# STLink_v21.net
KiCad netlist of a schematic drawn in EAGLE
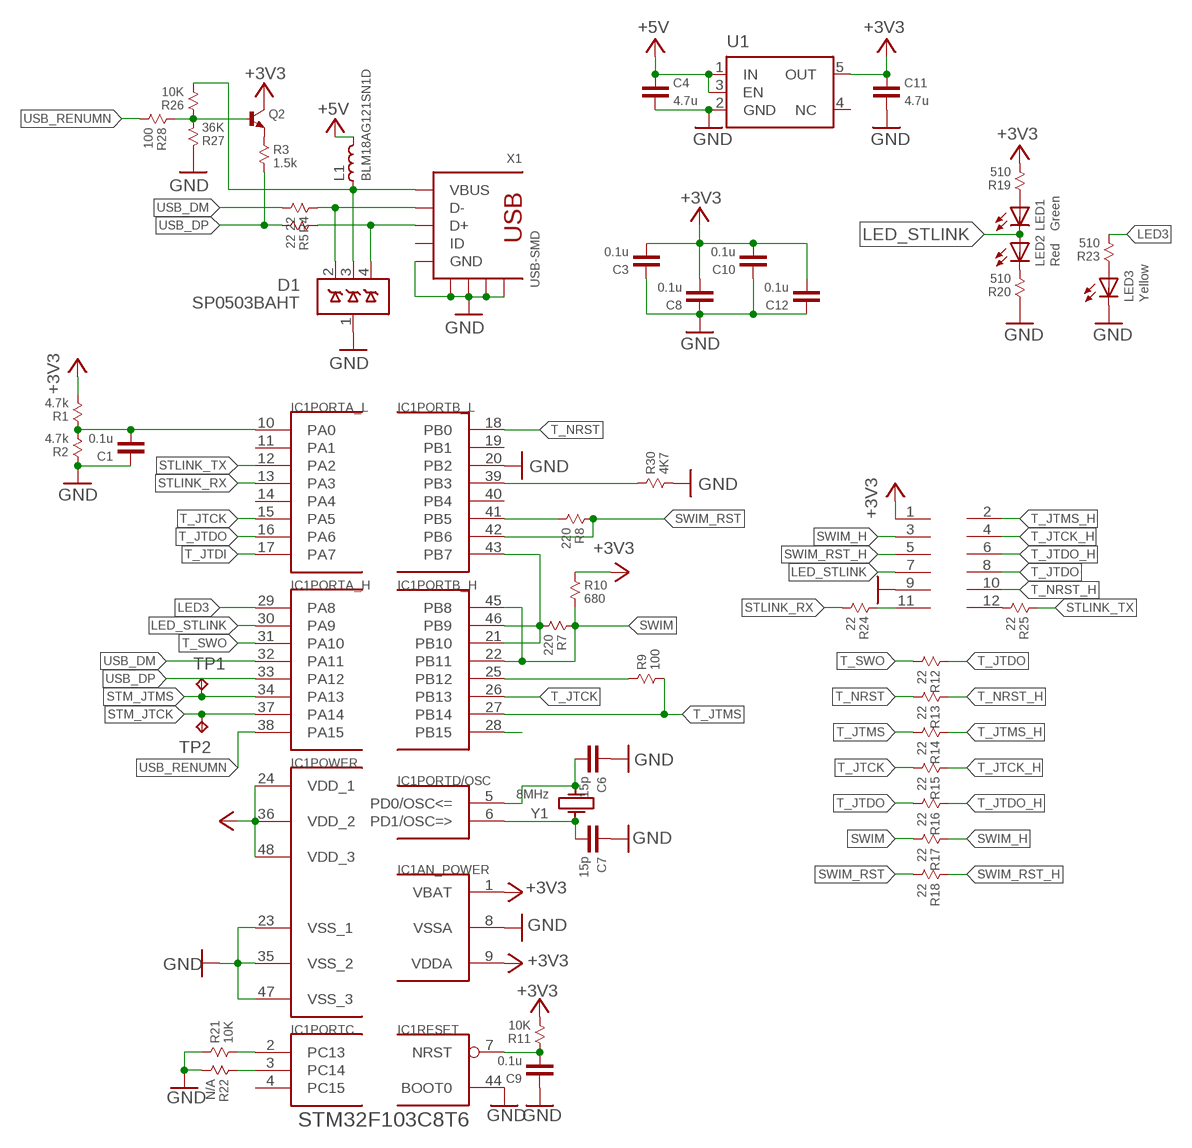
[diagram p0: schematic, sheet 1]

(export (version "E")
  (design (tool "Eeschema 10.0.6"))
  (components
    (comp (ref "C1")
      (value "0.1u")
      (footprint "eagle-import:0603")
      (libsource (lib "eagle-import") (part "CAP-0603"))
    )
    (comp (ref "C3")
      (value "0.1u")
      (footprint "eagle-import:0603")
      (libsource (lib "eagle-import") (part "CAP-0603"))
    )
    (comp (ref "C4")
      (value "4.7u")
      (footprint "eagle-import:0603")
      (libsource (lib "eagle-import") (part "CAP-0603"))
    )
    (comp (ref "C6")
      (value "15p")
      (footprint "eagle-import:0603")
      (libsource (lib "eagle-import") (part "CAP-0603"))
    )
    (comp (ref "C7")
      (value "15p")
      (footprint "eagle-import:0603")
      (libsource (lib "eagle-import") (part "CAP-0603"))
    )
    (comp (ref "C8")
      (value "0.1u")
      (footprint "eagle-import:0603")
      (libsource (lib "eagle-import") (part "CAP-0603"))
    )
    (comp (ref "C9")
      (value "0.1u")
      (footprint "eagle-import:0603")
      (libsource (lib "eagle-import") (part "CAP-0603"))
    )
    (comp (ref "C10")
      (value "0.1u")
      (footprint "eagle-import:0603")
      (libsource (lib "eagle-import") (part "CAP-0603"))
    )
    (comp (ref "C11")
      (value "4.7u")
      (footprint "eagle-import:0603")
      (libsource (lib "eagle-import") (part "CAP-0603"))
    )
    (comp (ref "C12")
      (value "0.1u")
      (footprint "eagle-import:0603")
      (libsource (lib "eagle-import") (part "CAP-0603"))
    )
    (comp (ref "CN2")
      (value "M06X2")
      (footprint "eagle-import:PLANAR-6X2")
      (libsource (lib "eagle-import") (part "M06X2"))
    )
    (comp (ref "D1")
      (value "SP0503BAHT")
      (footprint "eagle-import:SOT143")
      (libsource (lib "eagle-import") (part "SP0503BAHT"))
    )
    (comp (ref "IC1")
      (value "STM32F103C8T6")
      (footprint "eagle-import:TQFP48")
      (libsource (lib "eagle-import") (part "STM32F10XCXT6"))
    )
    (comp (ref "L1")
      (value "BLM18AG121SN1D")
      (footprint "eagle-import:0603")
      (libsource (lib "eagle-import") (part "INDUCTOR-0603"))
    )
    (comp (ref "LED1")
      (value "Green")
      (footprint "eagle-import:CHIP-LED0603")
      (libsource (lib "eagle-import") (part "LEDCHIP-LED0603"))
    )
    (comp (ref "LED2")
      (value "Red")
      (footprint "eagle-import:CHIP-LED0603")
      (libsource (lib "eagle-import") (part "LEDCHIP-LED0603"))
    )
    (comp (ref "LED3")
      (value "Yellow")
      (footprint "eagle-import:CHIP-LED0603")
      (libsource (lib "eagle-import") (part "LEDCHIP-LED0603"))
    )
    (comp (ref "Q2")
      (value "NPNBC847")
      (footprint "eagle-import:SOT-23")
      (libsource (lib "eagle-import") (part "NPNBC847"))
    )
    (comp (ref "R1")
      (value "4.7k")
      (footprint "eagle-import:0603")
      (libsource (lib "eagle-import") (part "RESISTOR-0603"))
    )
    (comp (ref "R2")
      (value "4.7k")
      (footprint "eagle-import:0603")
      (libsource (lib "eagle-import") (part "RESISTOR-0603"))
    )
    (comp (ref "R3")
      (value "1.5k")
      (footprint "eagle-import:0603")
      (libsource (lib "eagle-import") (part "RESISTOR-0603"))
    )
    (comp (ref "R4")
      (value "22")
      (footprint "eagle-import:0603")
      (libsource (lib "eagle-import") (part "RESISTOR-0603"))
    )
    (comp (ref "R5")
      (value "22")
      (footprint "eagle-import:0603")
      (libsource (lib "eagle-import") (part "RESISTOR-0603"))
    )
    (comp (ref "R7")
      (value "220")
      (footprint "eagle-import:0603")
      (libsource (lib "eagle-import") (part "RESISTOR-0603"))
    )
    (comp (ref "R8")
      (value "220")
      (footprint "eagle-import:0603")
      (libsource (lib "eagle-import") (part "RESISTOR-0603"))
    )
    (comp (ref "R9")
      (value "100")
      (footprint "eagle-import:0603")
      (libsource (lib "eagle-import") (part "RESISTOR-0603"))
    )
    (comp (ref "R10")
      (value "680")
      (footprint "eagle-import:0603")
      (libsource (lib "eagle-import") (part "RESISTOR-0603"))
    )
    (comp (ref "R11")
      (value "10K")
      (footprint "eagle-import:0603")
      (libsource (lib "eagle-import") (part "RESISTOR-0603"))
    )
    (comp (ref "R12")
      (value "22")
      (footprint "eagle-import:0603")
      (libsource (lib "eagle-import") (part "RESISTOR-0603"))
    )
    (comp (ref "R13")
      (value "22")
      (footprint "eagle-import:0603")
      (libsource (lib "eagle-import") (part "RESISTOR-0603"))
    )
    (comp (ref "R14")
      (value "22")
      (footprint "eagle-import:0603")
      (libsource (lib "eagle-import") (part "RESISTOR-0603"))
    )
    (comp (ref "R15")
      (value "22")
      (footprint "eagle-import:0603")
      (libsource (lib "eagle-import") (part "RESISTOR-0603"))
    )
    (comp (ref "R16")
      (value "22")
      (footprint "eagle-import:0603")
      (libsource (lib "eagle-import") (part "RESISTOR-0603"))
    )
    (comp (ref "R17")
      (value "22")
      (footprint "eagle-import:0603")
      (libsource (lib "eagle-import") (part "RESISTOR-0603"))
    )
    (comp (ref "R18")
      (value "22")
      (footprint "eagle-import:0603")
      (libsource (lib "eagle-import") (part "RESISTOR-0603"))
    )
    (comp (ref "R19")
      (value "510")
      (footprint "eagle-import:0603")
      (libsource (lib "eagle-import") (part "RESISTOR-0603"))
    )
    (comp (ref "R20")
      (value "510")
      (footprint "eagle-import:0603")
      (libsource (lib "eagle-import") (part "RESISTOR-0603"))
    )
    (comp (ref "R21")
      (value "10K")
      (footprint "eagle-import:0603")
      (libsource (lib "eagle-import") (part "RESISTOR-0603"))
    )
    (comp (ref "R22")
      (value "N/A")
      (footprint "eagle-import:0603")
      (libsource (lib "eagle-import") (part "RESISTOR-0603"))
    )
    (comp (ref "R23")
      (value "510")
      (footprint "eagle-import:0603")
      (libsource (lib "eagle-import") (part "RESISTOR-0603"))
    )
    (comp (ref "R24")
      (value "22")
      (footprint "eagle-import:0603")
      (libsource (lib "eagle-import") (part "RESISTOR-0603"))
    )
    (comp (ref "R25")
      (value "22")
      (footprint "eagle-import:0603")
      (libsource (lib "eagle-import") (part "RESISTOR-0603"))
    )
    (comp (ref "R26")
      (value "10K")
      (footprint "eagle-import:0603")
      (libsource (lib "eagle-import") (part "RESISTOR-0603"))
    )
    (comp (ref "R27")
      (value "36K")
      (footprint "eagle-import:0603")
      (libsource (lib "eagle-import") (part "RESISTOR-0603"))
    )
    (comp (ref "R28")
      (value "100")
      (footprint "eagle-import:0603")
      (libsource (lib "eagle-import") (part "RESISTOR-0603"))
    )
    (comp (ref "R30")
      (value "4K7")
      (footprint "eagle-import:0603")
      (libsource (lib "eagle-import") (part "RESISTOR-0603"))
    )
    (comp (ref "TP1")
      (value "TPTP10R")
      (footprint "eagle-import:TP10R")
      (libsource (lib "eagle-import") (part "TPTP10R"))
    )
    (comp (ref "TP2")
      (value "TPTP10R")
      (footprint "eagle-import:TP10R")
      (libsource (lib "eagle-import") (part "TPTP10R"))
    )
    (comp (ref "U1")
      (value "TPS73033")
      (footprint "eagle-import:SOT23-5")
      (libsource (lib "eagle-import") (part "TPS73033"))
    )
    (comp (ref "X1")
      (value "USB-SMD")
      (footprint "eagle-import:USB-MINIB")
      (libsource (lib "eagle-import") (part "USB-SMD"))
    )
    (comp (ref "Y1")
      (value "8MHz")
      (footprint "eagle-import:C0532")
      (libsource (lib "eagle-import") (part "CRYSTAL-0532"))
    )
  )
  (nets
    (net (code "1") (name "+3V3") (class "Default")
      (node (ref "C10") (pin "1") (pinfunction "1_1") (pintype "passive"))
      (node (ref "C11") (pin "2") (pinfunction "2_2") (pintype "passive"))
      (node (ref "C12") (pin "1") (pinfunction "1_1") (pintype "passive"))
      (node (ref "C3") (pin "1") (pinfunction "1_1") (pintype "passive"))
      (node (ref "C8") (pin "1") (pinfunction "1_1") (pintype "passive"))
      (node (ref "CN2") (pin "1") (pinfunction "1_1") (pintype "bidirectional"))
      (node (ref "IC1") (pin "1") (pinfunction "VBAT_1") (pintype "power_in"))
      (node (ref "IC1") (pin "24") (pinfunction "VDD_1_24") (pintype "power_in"))
      (node (ref "IC1") (pin "36") (pinfunction "VDD_2_36") (pintype "power_in"))
      (node (ref "IC1") (pin "48") (pinfunction "VDD_3_48") (pintype "power_in"))
      (node (ref "IC1") (pin "9") (pinfunction "VDDA_9") (pintype "power_in"))
      (node (ref "Q2") (pin "3") (pinfunction "C_3") (pintype "passive"))
      (node (ref "R1") (pin "2") (pinfunction "2_2") (pintype "passive"))
      (node (ref "R10") (pin "1") (pinfunction "1_1") (pintype "passive"))
      (node (ref "R11") (pin "2") (pinfunction "2_2") (pintype "passive"))
      (node (ref "R19") (pin "2") (pinfunction "2_2") (pintype "passive"))
      (node (ref "U1") (pin "5") (pinfunction "OUT_5") (pintype "passive"))
    )
    (net (code "2") (name "+5V") (class "Default")
      (node (ref "C4") (pin "2") (pinfunction "2_2") (pintype "passive"))
      (node (ref "L1") (pin "2") (pinfunction "2_2") (pintype "passive"))
      (node (ref "U1") (pin "1") (pinfunction "IN_1") (pintype "passive"))
      (node (ref "U1") (pin "3") (pinfunction "EN_3") (pintype "input"))
    )
    (net (code "3") (name "GND") (class "Default")
      (node (ref "C1") (pin "2") (pinfunction "2_2") (pintype "passive"))
      (node (ref "C10") (pin "2") (pinfunction "2_2") (pintype "passive"))
      (node (ref "C11") (pin "1") (pinfunction "1_1") (pintype "passive"))
      (node (ref "C12") (pin "2") (pinfunction "2_2") (pintype "passive"))
      (node (ref "C3") (pin "2") (pinfunction "2_2") (pintype "passive"))
      (node (ref "C4") (pin "1") (pinfunction "1_1") (pintype "passive"))
      (node (ref "C6") (pin "2") (pinfunction "2_2") (pintype "passive"))
      (node (ref "C7") (pin "2") (pinfunction "2_2") (pintype "passive"))
      (node (ref "C8") (pin "2") (pinfunction "2_2") (pintype "passive"))
      (node (ref "C9") (pin "2") (pinfunction "2_2") (pintype "passive"))
      (node (ref "CN2") (pin "9") (pinfunction "9_9") (pintype "bidirectional"))
      (node (ref "D1") (pin "1") (pinfunction "GND_1") (pintype "power_in"))
      (node (ref "IC1") (pin "20") (pinfunction "PB2_20") (pintype "bidirectional"))
      (node (ref "IC1") (pin "23") (pinfunction "VSS_1_23") (pintype "power_in"))
      (node (ref "IC1") (pin "35") (pinfunction "VSS_2_35") (pintype "power_in"))
      (node (ref "IC1") (pin "44") (pinfunction "BOOT0_44") (pintype "input"))
      (node (ref "IC1") (pin "47") (pinfunction "VSS_3_47") (pintype "power_in"))
      (node (ref "IC1") (pin "8") (pinfunction "VSSA_8") (pintype "power_in"))
      (node (ref "LED3") (pin "C") (pinfunction "C_C") (pintype "passive"))
      (node (ref "R2") (pin "1") (pinfunction "1_1") (pintype "passive"))
      (node (ref "R20") (pin "1") (pinfunction "1_1") (pintype "passive"))
      (node (ref "R21") (pin "1") (pinfunction "1_1") (pintype "passive"))
      (node (ref "R22") (pin "2") (pinfunction "2_2") (pintype "passive"))
      (node (ref "R27") (pin "1") (pinfunction "1_1") (pintype "passive"))
      (node (ref "R30") (pin "2") (pinfunction "2_2") (pintype "passive"))
      (node (ref "U1") (pin "2") (pinfunction "GND_2") (pintype "power_in"))
      (node (ref "X1") (pin "GND") (pinfunction "GND_GND") (pintype "power_in"))
      (node (ref "X1") (pin "GND@1") (pinfunction "GND_GND@1") (pintype "power_in"))
      (node (ref "X1") (pin "GND@2") (pinfunction "GND_GND@2") (pintype "power_in"))
      (node (ref "X1") (pin "GND@3") (pinfunction "GND_GND@3") (pintype "power_in"))
      (node (ref "X1") (pin "GND@4") (pinfunction "GND_GND@4") (pintype "power_in"))
    )
    (net (code "4") (name "LED3") (class "Default")
      (node (ref "IC1") (pin "29") (pinfunction "PA8_29") (pintype "bidirectional"))
      (node (ref "R23") (pin "2") (pinfunction "2_2") (pintype "passive"))
    )
    (net (code "5") (name "LED_STLINK") (class "Default")
      (node (ref "CN2") (pin "7") (pinfunction "7_7") (pintype "bidirectional"))
      (node (ref "IC1") (pin "30") (pinfunction "PA9_30") (pintype "bidirectional"))
      (node (ref "LED1") (pin "C") (pinfunction "C_C") (pintype "passive"))
      (node (ref "LED2") (pin "A") (pinfunction "A_A") (pintype "passive"))
    )
    (net (code "6") (name "Net-(CN2-Pad11)") (class "Default")
      (node (ref "CN2") (pin "11") (pinfunction "11_11") (pintype "bidirectional"))
      (node (ref "R24") (pin "1") (pinfunction "1_1") (pintype "passive"))
    )
    (net (code "7") (name "Net-(CN2-Pad12)") (class "Default")
      (node (ref "CN2") (pin "12") (pinfunction "12_12") (pintype "bidirectional"))
      (node (ref "R25") (pin "2") (pinfunction "2_2") (pintype "passive"))
    )
    (net (code "8") (name "Net-(D1-D1)") (class "Default")
      (node (ref "D1") (pin "2") (pinfunction "D1_2") (pintype "passive"))
      (node (ref "R4") (pin "1") (pinfunction "1_1") (pintype "passive"))
      (node (ref "X1") (pin "D-") (pinfunction "D-_D-") (pintype "bidirectional"))
    )
    (net (code "9") (name "Net-(D1-D2)") (class "Default")
      (node (ref "D1") (pin "3") (pinfunction "D2_3") (pintype "passive"))
      (node (ref "L1") (pin "1") (pinfunction "1_1") (pintype "passive"))
      (node (ref "R26") (pin "2") (pinfunction "2_2") (pintype "passive"))
      (node (ref "X1") (pin "VBUS") (pinfunction "VBUS_VBUS") (pintype "passive"))
    )
    (net (code "10") (name "Net-(D1-D3)") (class "Default")
      (node (ref "D1") (pin "4") (pinfunction "D3_4") (pintype "passive"))
      (node (ref "R5") (pin "1") (pinfunction "1_1") (pintype "passive"))
      (node (ref "X1") (pin "D+") (pinfunction "D+_D+") (pintype "bidirectional"))
    )
    (net (code "11") (name "Net-(IC1C-PA0)") (class "Default")
      (node (ref "C1") (pin "1") (pinfunction "1_1") (pintype "passive"))
      (node (ref "IC1") (pin "10") (pinfunction "PA0_10") (pintype "bidirectional"))
      (node (ref "R1") (pin "1") (pinfunction "1_1") (pintype "passive"))
      (node (ref "R2") (pin "2") (pinfunction "2_2") (pintype "passive"))
    )
    (net (code "12") (name "Net-(IC1D-PB10)") (class "Default")
      (node (ref "IC1") (pin "21") (pinfunction "PB10_21") (pintype "bidirectional"))
      (node (ref "IC1") (pin "43") (pinfunction "PB7_43") (pintype "bidirectional"))
      (node (ref "IC1") (pin "46") (pinfunction "PB9_46") (pintype "bidirectional"))
      (node (ref "R7") (pin "2") (pinfunction "2_2") (pintype "passive"))
    )
    (net (code "13") (name "Net-(IC1D-PB12)") (class "Default")
      (node (ref "IC1") (pin "25") (pinfunction "PB12_25") (pintype "bidirectional"))
      (node (ref "R9") (pin "1") (pinfunction "1_1") (pintype "passive"))
    )
    (net (code "14") (name "Net-(IC1E-PB3)") (class "Default")
      (node (ref "IC1") (pin "39") (pinfunction "PB3_39") (pintype "bidirectional"))
      (node (ref "R30") (pin "1") (pinfunction "1_1") (pintype "passive"))
    )
    (net (code "15") (name "Net-(IC1E-PB5)") (class "Default")
      (node (ref "IC1") (pin "41") (pinfunction "PB5_41") (pintype "bidirectional"))
      (node (ref "R8") (pin "2") (pinfunction "2_2") (pintype "passive"))
    )
    (net (code "16") (name "Net-(IC1F-PC13)") (class "Default")
      (node (ref "IC1") (pin "2") (pinfunction "PC13_2") (pintype "bidirectional"))
      (node (ref "R21") (pin "2") (pinfunction "2_2") (pintype "passive"))
    )
    (net (code "17") (name "Net-(IC1F-PC14)") (class "Default")
      (node (ref "IC1") (pin "3") (pinfunction "PC14_3") (pintype "bidirectional"))
      (node (ref "R22") (pin "1") (pinfunction "1_1") (pintype "passive"))
    )
    (net (code "18") (name "Net-(IC1G-PD0{slash}OSC<=)") (class "Default")
      (node (ref "C6") (pin "1") (pinfunction "1_1") (pintype "passive"))
      (node (ref "IC1") (pin "5") (pinfunction "PD0/OSC<=_5") (pintype "bidirectional"))
      (node (ref "Y1") (pin "3") (pinfunction "2_3") (pintype "passive"))
    )
    (net (code "19") (name "Net-(IC1G-PD1{slash}OSC=>)") (class "Default")
      (node (ref "C7") (pin "1") (pinfunction "1_1") (pintype "passive"))
      (node (ref "IC1") (pin "6") (pinfunction "PD1/OSC=>_6") (pintype "bidirectional"))
      (node (ref "Y1") (pin "1") (pinfunction "1_1") (pintype "passive"))
    )
    (net (code "20") (name "Net-(IC1I-NRST)") (class "Default")
      (node (ref "C9") (pin "1") (pinfunction "1_1") (pintype "passive"))
      (node (ref "IC1") (pin "7") (pinfunction "NRST_7") (pintype "input"))
      (node (ref "R11") (pin "1") (pinfunction "1_1") (pintype "passive"))
    )
    (net (code "21") (name "Net-(LED1-PadA)") (class "Default")
      (node (ref "LED1") (pin "A") (pinfunction "A_A") (pintype "passive"))
      (node (ref "R19") (pin "1") (pinfunction "1_1") (pintype "passive"))
    )
    (net (code "22") (name "Net-(LED2-PadC)") (class "Default")
      (node (ref "LED2") (pin "C") (pinfunction "C_C") (pintype "passive"))
      (node (ref "R20") (pin "2") (pinfunction "2_2") (pintype "passive"))
    )
    (net (code "23") (name "Net-(LED3-PadA)") (class "Default")
      (node (ref "LED3") (pin "A") (pinfunction "A_A") (pintype "passive"))
      (node (ref "R23") (pin "1") (pinfunction "1_1") (pintype "passive"))
    )
    (net (code "24") (name "Net-(Q2-B)") (class "Default")
      (node (ref "Q2") (pin "1") (pinfunction "B_1") (pintype "passive"))
      (node (ref "R26") (pin "1") (pinfunction "1_1") (pintype "passive"))
      (node (ref "R27") (pin "2") (pinfunction "2_2") (pintype "passive"))
      (node (ref "R28") (pin "1") (pinfunction "1_1") (pintype "passive"))
    )
    (net (code "25") (name "Net-(Q2-E)") (class "Default")
      (node (ref "Q2") (pin "2") (pinfunction "E_2") (pintype "passive"))
      (node (ref "R3") (pin "1") (pinfunction "1_1") (pintype "passive"))
    )
    (net (code "26") (name "STLINK_RX") (class "Default")
      (node (ref "IC1") (pin "13") (pinfunction "PA3_13") (pintype "bidirectional"))
      (node (ref "R24") (pin "2") (pinfunction "2_2") (pintype "passive"))
    )
    (net (code "27") (name "STLINK_TX") (class "Default")
      (node (ref "IC1") (pin "12") (pinfunction "PA2_12") (pintype "bidirectional"))
      (node (ref "R25") (pin "1") (pinfunction "1_1") (pintype "passive"))
    )
    (net (code "28") (name "STM_JTCK") (class "Default")
      (node (ref "IC1") (pin "37") (pinfunction "PA14_37") (pintype "bidirectional"))
      (node (ref "TP2") (pin "TP") (pinfunction "TP_TP") (pintype "input"))
    )
    (net (code "29") (name "STM_JTMS") (class "Default")
      (node (ref "IC1") (pin "34") (pinfunction "PA13_34") (pintype "bidirectional"))
      (node (ref "TP1") (pin "TP") (pinfunction "TP_TP") (pintype "input"))
    )
    (net (code "30") (name "SWIM") (class "Default")
      (node (ref "IC1") (pin "22") (pinfunction "PB11_22") (pintype "bidirectional"))
      (node (ref "IC1") (pin "45") (pinfunction "PB8_45") (pintype "bidirectional"))
      (node (ref "R10") (pin "2") (pinfunction "2_2") (pintype "passive"))
      (node (ref "R17") (pin "2") (pinfunction "2_2") (pintype "passive"))
      (node (ref "R7") (pin "1") (pinfunction "1_1") (pintype "passive"))
    )
    (net (code "31") (name "SWIM_H") (class "Default")
      (node (ref "CN2") (pin "3") (pinfunction "3_3") (pintype "bidirectional"))
      (node (ref "R17") (pin "1") (pinfunction "1_1") (pintype "passive"))
    )
    (net (code "32") (name "SWIM_RST") (class "Default")
      (node (ref "IC1") (pin "42") (pinfunction "PB6_42") (pintype "bidirectional"))
      (node (ref "R18") (pin "2") (pinfunction "2_2") (pintype "passive"))
      (node (ref "R8") (pin "1") (pinfunction "1_1") (pintype "passive"))
    )
    (net (code "33") (name "SWIM_RST_H") (class "Default")
      (node (ref "CN2") (pin "5") (pinfunction "5_5") (pintype "bidirectional"))
      (node (ref "R18") (pin "1") (pinfunction "1_1") (pintype "passive"))
    )
    (net (code "34") (name "T_JTCK") (class "Default")
      (node (ref "IC1") (pin "15") (pinfunction "PA5_15") (pintype "bidirectional"))
      (node (ref "IC1") (pin "26") (pinfunction "PB13_26") (pintype "bidirectional"))
      (node (ref "R15") (pin "2") (pinfunction "2_2") (pintype "passive"))
    )
    (net (code "35") (name "T_JTCK_H") (class "Default")
      (node (ref "CN2") (pin "4") (pinfunction "4_4") (pintype "bidirectional"))
      (node (ref "R15") (pin "1") (pinfunction "1_1") (pintype "passive"))
    )
    (net (code "36") (name "T_JTDI") (class "Default")
      (node (ref "IC1") (pin "17") (pinfunction "PA7_17") (pintype "bidirectional"))
    )
    (net (code "37") (name "T_JTDO") (class "Default")
      (node (ref "CN2") (pin "8") (pinfunction "8_8") (pintype "bidirectional"))
      (node (ref "IC1") (pin "16") (pinfunction "PA6_16") (pintype "bidirectional"))
      (node (ref "R12") (pin "1") (pinfunction "1_1") (pintype "passive"))
      (node (ref "R16") (pin "2") (pinfunction "2_2") (pintype "passive"))
    )
    (net (code "38") (name "T_JTDO_H") (class "Default")
      (node (ref "CN2") (pin "6") (pinfunction "6_6") (pintype "bidirectional"))
      (node (ref "R16") (pin "1") (pinfunction "1_1") (pintype "passive"))
    )
    (net (code "39") (name "T_JTMS") (class "Default")
      (node (ref "IC1") (pin "27") (pinfunction "PB14_27") (pintype "bidirectional"))
      (node (ref "R14") (pin "2") (pinfunction "2_2") (pintype "passive"))
      (node (ref "R9") (pin "2") (pinfunction "2_2") (pintype "passive"))
    )
    (net (code "40") (name "T_JTMS_H") (class "Default")
      (node (ref "CN2") (pin "2") (pinfunction "2_2") (pintype "bidirectional"))
      (node (ref "R14") (pin "1") (pinfunction "1_1") (pintype "passive"))
    )
    (net (code "41") (name "T_NRST") (class "Default")
      (node (ref "IC1") (pin "18") (pinfunction "PB0_18") (pintype "bidirectional"))
      (node (ref "R13") (pin "2") (pinfunction "2_2") (pintype "passive"))
    )
    (net (code "42") (name "T_NRST_H") (class "Default")
      (node (ref "CN2") (pin "10") (pinfunction "10_10") (pintype "bidirectional"))
      (node (ref "R13") (pin "1") (pinfunction "1_1") (pintype "passive"))
    )
    (net (code "43") (name "T_SWO") (class "Default")
      (node (ref "IC1") (pin "31") (pinfunction "PA10_31") (pintype "bidirectional"))
      (node (ref "R12") (pin "2") (pinfunction "2_2") (pintype "passive"))
    )
    (net (code "44") (name "USB_DM") (class "Default")
      (node (ref "IC1") (pin "32") (pinfunction "PA11_32") (pintype "bidirectional"))
      (node (ref "R4") (pin "2") (pinfunction "2_2") (pintype "passive"))
    )
    (net (code "45") (name "USB_DP") (class "Default")
      (node (ref "IC1") (pin "33") (pinfunction "PA12_33") (pintype "bidirectional"))
      (node (ref "R3") (pin "2") (pinfunction "2_2") (pintype "passive"))
      (node (ref "R5") (pin "2") (pinfunction "2_2") (pintype "passive"))
    )
    (net (code "46") (name "USB_RENUMN") (class "Default")
      (node (ref "IC1") (pin "38") (pinfunction "PA15_38") (pintype "bidirectional"))
      (node (ref "R28") (pin "2") (pinfunction "2_2") (pintype "passive"))
    )
    (net (code "47") (name "unconnected-(IC1C-PA1-Pad11)") (class "Default")
      (node (ref "IC1") (pin "11") (pinfunction "PA1_11") (pintype "bidirectional"))
    )
    (net (code "48") (name "unconnected-(IC1C-PA4-Pad14)") (class "Default")
      (node (ref "IC1") (pin "14") (pinfunction "PA4_14") (pintype "bidirectional"))
    )
    (net (code "49") (name "unconnected-(IC1D-PB15-Pad28)") (class "Default")
      (node (ref "IC1") (pin "28") (pinfunction "PB15_28") (pintype "bidirectional"))
    )
    (net (code "50") (name "unconnected-(IC1E-PB1-Pad19)") (class "Default")
      (node (ref "IC1") (pin "19") (pinfunction "PB1_19") (pintype "bidirectional"))
    )
    (net (code "51") (name "unconnected-(IC1E-PB4-Pad40)") (class "Default")
      (node (ref "IC1") (pin "40") (pinfunction "PB4_40") (pintype "bidirectional"))
    )
    (net (code "52") (name "unconnected-(IC1F-PC15-Pad4)") (class "Default")
      (node (ref "IC1") (pin "4") (pinfunction "PC15_4") (pintype "bidirectional"))
    )
    (net (code "53") (name "unconnected-(U1-NC-Pad4)") (class "Default")
      (node (ref "U1") (pin "4") (pinfunction "NC_4") (pintype "no_connect"))
    )
    (net (code "54") (name "unconnected-(X1-PadID)") (class "Default")
      (node (ref "X1") (pin "ID") (pinfunction "ID_ID") (pintype "bidirectional"))
    )
  )
)
